# adc.net
KiCad netlist of a schematic drawn in Altium Designer
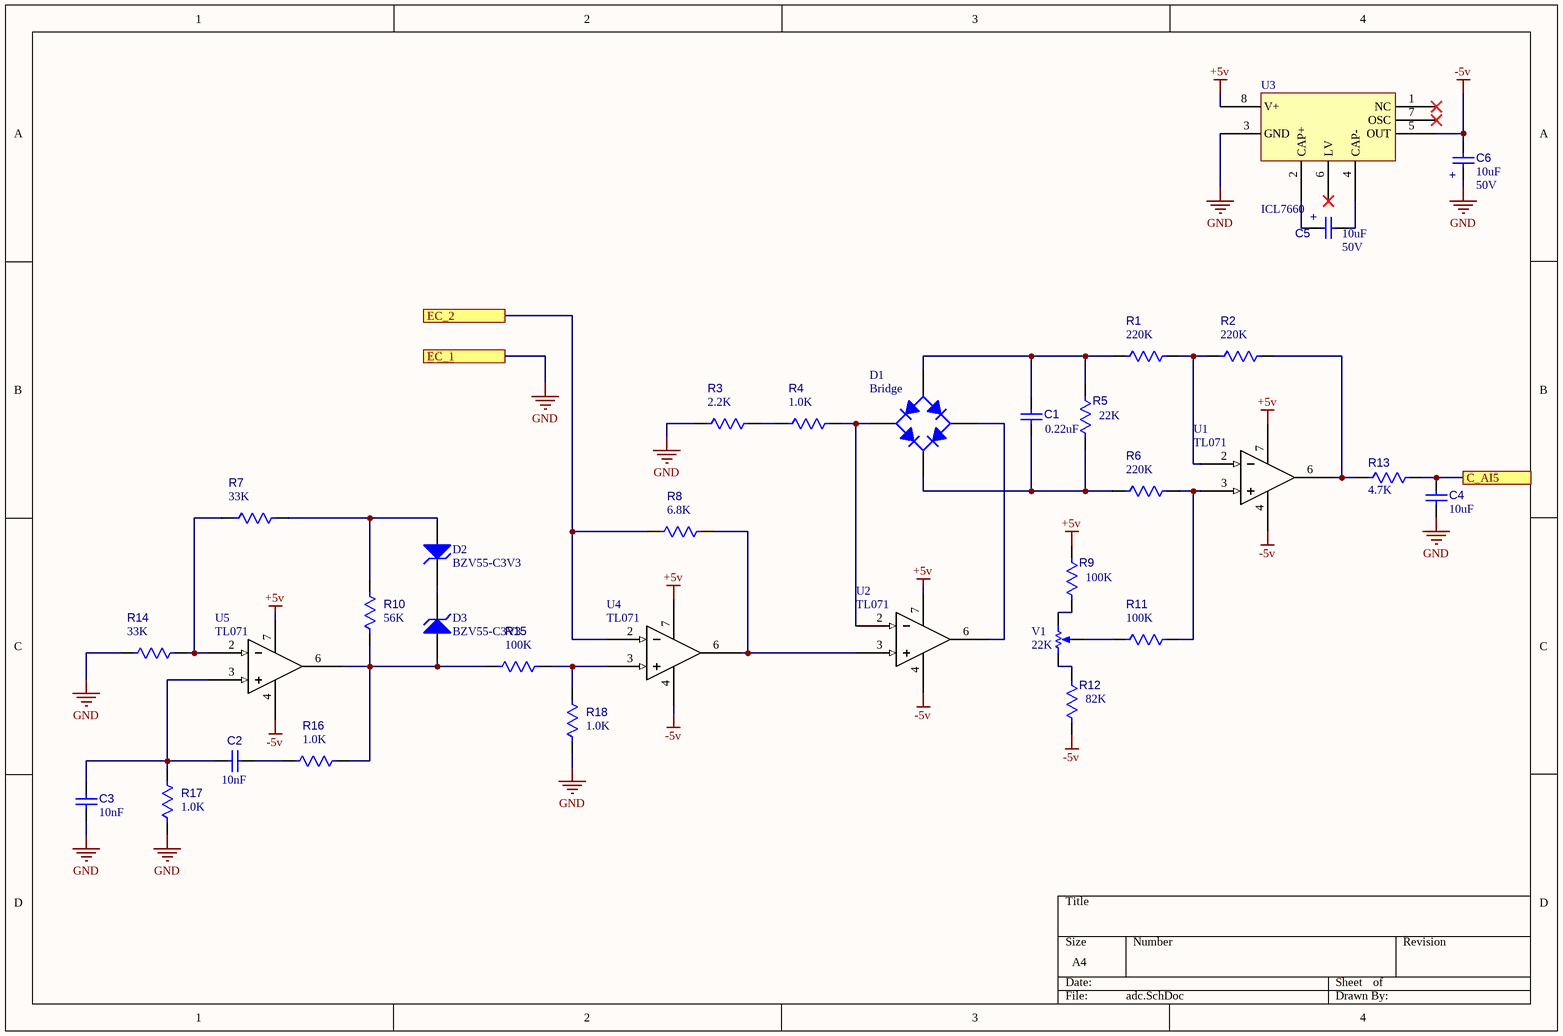
[diagram p0: adc.SchDoc]

(export (version "E")
  (design (tool "Eeschema 10.0.6"))
  (components
    (comp (ref "C1")
      (value "0.22uF")
      (footprint "0805")
      (description "Cap")
      (fields (field (name "TOLERANCE") "±10%"))
      (libsource (lib "mylib") (part "Cap"))
    )
    (comp (ref "C2")
      (value "10nF")
      (footprint "0805")
      (description "Cap")
      (fields (field (name "TOLERANCE") "±10%"))
      (libsource (lib "mylib") (part "Cap"))
    )
    (comp (ref "C3")
      (value "10nF")
      (footprint "0805")
      (description "Cap")
      (fields (field (name "TOLERANCE") "±10%"))
      (libsource (lib "mylib") (part "Cap"))
    )
    (comp (ref "C4")
      (value "10uF")
      (footprint "CAPC3216x130N")
      (description "Cap")
      (fields (field (name "TOLERANCE") "±10%"))
      (libsource (lib "mylib") (part "Cap"))
    )
    (comp (ref "C5")
      (value "10uF")
      (footprint "CAPC3216x130N")
      (description "Cap")
      (fields
        (field (name "TOLERANCE") "±10%")
        (field (name "MANUFACTURER") "Panasonic")
        (field (name "VOLTAGE-RATED") "50V")
      )
      (libsource (lib "mylib") (part "Cap Pol"))
    )
    (comp (ref "C6")
      (value "10uF")
      (footprint "CAPC3216x130N")
      (description "Cap")
      (fields
        (field (name "TOLERANCE") "±10%")
        (field (name "MANUFACTURER") "Panasonic")
        (field (name "VOLTAGE-RATED") "50V")
      )
      (libsource (lib "mylib") (part "Cap Pol"))
    )
    (comp (ref "D1")
      (value "Bridge")
      (footprint "BRIDGE_TO-269AA")
      (description "Full Wave Diode Bridge")
      (fields (field (name "PUBLISHER") "Altium Limited"))
      (libsource (lib "mylib") (part "Bridge"))
    )
    (comp (ref "D2")
      (value "BZV55-C3V3")
      (footprint "SOD80C")
      (description "Zener Diode 3.3v - SMD")
      (fields (field (name "PUBLISHER") "Altium Limited"))
      (libsource (lib "mylib") (part "D Zener"))
    )
    (comp (ref "D3")
      (value "BZV55-C3V3")
      (footprint "SOD80C")
      (description "Zener Diode 3.3v - SMD")
      (fields (field (name "PUBLISHER") "Altium Limited"))
      (libsource (lib "mylib") (part "D Zener"))
    )
    (comp (ref "R1")
      (value "220K")
      (footprint "0805")
      (description "Resistor")
      (fields (field (name "TOLERANCE") "1%"))
      (libsource (lib "mylib") (part "Res"))
    )
    (comp (ref "R2")
      (value "220K")
      (footprint "0805")
      (description "Resistor")
      (fields (field (name "TOLERANCE") "1%"))
      (libsource (lib "mylib") (part "Res"))
    )
    (comp (ref "R3")
      (value "2.2K")
      (footprint "0805")
      (description "Resistor")
      (fields (field (name "TOLERANCE") "1%"))
      (libsource (lib "mylib") (part "Res"))
    )
    (comp (ref "R4")
      (value "1.0K")
      (footprint "0805")
      (description "Resistor")
      (fields (field (name "TOLERANCE") "1%"))
      (libsource (lib "mylib") (part "Res"))
    )
    (comp (ref "R5")
      (value "22K")
      (footprint "0805")
      (description "Resistor")
      (fields (field (name "TOLERANCE") "1%"))
      (libsource (lib "mylib") (part "Res"))
    )
    (comp (ref "R6")
      (value "220K")
      (footprint "0805")
      (description "Resistor")
      (fields (field (name "TOLERANCE") "1%"))
      (libsource (lib "mylib") (part "Res"))
    )
    (comp (ref "R7")
      (value "33K")
      (footprint "0805")
      (description "Resistor")
      (fields (field (name "TOLERANCE") "1%"))
      (libsource (lib "mylib") (part "Res"))
    )
    (comp (ref "R8")
      (value "6.8K")
      (footprint "mylib:0603")
      (description "Resistor")
      (fields (field (name "TOLERANCE") "1%"))
      (libsource (lib "mylib") (part "Res"))
    )
    (comp (ref "R9")
      (value "100K")
      (footprint "0805")
      (description "Resistor")
      (fields (field (name "TOLERANCE") "1%"))
      (libsource (lib "mylib") (part "Res"))
    )
    (comp (ref "R10")
      (value "56K")
      (footprint "mylib:0603")
      (description "Resistor")
      (fields (field (name "TOLERANCE") "1%"))
      (libsource (lib "mylib") (part "Res"))
    )
    (comp (ref "R11")
      (value "100K")
      (footprint "0805")
      (description "Resistor")
      (fields (field (name "TOLERANCE") "1%"))
      (libsource (lib "mylib") (part "Res"))
    )
    (comp (ref "R12")
      (value "82K")
      (footprint "mylib:0603")
      (description "Resistor")
      (fields (field (name "TOLERANCE") "1%"))
      (libsource (lib "mylib") (part "Res"))
    )
    (comp (ref "R13")
      (value "4.7K")
      (footprint "0805")
      (description "Resistor")
      (fields (field (name "TOLERANCE") "1%"))
      (libsource (lib "mylib") (part "Res"))
    )
    (comp (ref "R14")
      (value "33K")
      (footprint "0805")
      (description "Resistor")
      (fields (field (name "TOLERANCE") "1%"))
      (libsource (lib "mylib") (part "Res"))
    )
    (comp (ref "R15")
      (value "100K")
      (footprint "0805")
      (description "Resistor")
      (fields (field (name "TOLERANCE") "1%"))
      (libsource (lib "mylib") (part "Res"))
    )
    (comp (ref "R16")
      (value "1.0K")
      (footprint "0805")
      (description "Resistor")
      (fields (field (name "TOLERANCE") "1%"))
      (libsource (lib "mylib") (part "Res"))
    )
    (comp (ref "R17")
      (value "1.0K")
      (footprint "0805")
      (description "Resistor")
      (fields (field (name "TOLERANCE") "1%"))
      (libsource (lib "mylib") (part "Res"))
    )
    (comp (ref "R18")
      (value "1.0K")
      (footprint "0805")
      (description "Resistor")
      (fields (field (name "TOLERANCE") "1%"))
      (libsource (lib "mylib") (part "Res"))
    )
    (comp (ref "U1")
      (value "TL071")
      (footprint "SO8_L")
      (description "Low-noise jfet-input operational amplifiers")
      (libsource (lib "mylib") (part "TL071"))
    )
    (comp (ref "U2")
      (value "TL071")
      (footprint "SO8_L")
      (description "Low-noise jfet-input operational amplifiers")
      (libsource (lib "mylib") (part "TL071"))
    )
    (comp (ref "U3")
      (value "ICL7660")
      (footprint "SO8_N")
      (description "CMOS Voltage Converters, from positive to negative for an input range of +1.5V to +10.0V")
      (libsource (lib "mylib") (part "ICL7660"))
    )
    (comp (ref "U4")
      (value "TL071")
      (footprint "SO8_L")
      (description "Low-noise jfet-input operational amplifiers")
      (libsource (lib "mylib") (part "TL071"))
    )
    (comp (ref "U5")
      (value "TL071")
      (footprint "SO8_L")
      (description "Low-noise jfet-input operational amplifiers")
      (libsource (lib "mylib") (part "TL071"))
    )
    (comp (ref "V1")
      (value "22K")
      (footprint "HDR1X3")
      (description "Potentiometer")
      (fields (field (name "PUBLISHER") "Altium Limited"))
      (libsource (lib "mylib") (part "Preset"))
    )
  )
  (nets
    (net (code "1") (name "+5v") (class "Default")
      (node (ref "R9") (pin "2") (pinfunction "2_2") (pintype "passive"))
      (node (ref "U1") (pin "7") (pinfunction "+Vcc_7") (pintype "passive"))
      (node (ref "U2") (pin "7") (pinfunction "+Vcc_7") (pintype "passive"))
      (node (ref "U3") (pin "8") (pinfunction "V+_8") (pintype "passive"))
      (node (ref "U4") (pin "7") (pinfunction "+Vcc_7") (pintype "passive"))
      (node (ref "U5") (pin "7") (pinfunction "+Vcc_7") (pintype "passive"))
    )
    (net (code "2") (name "-5v") (class "Default")
      (node (ref "C6") (pin "2") (pinfunction "2_2") (pintype "passive"))
      (node (ref "R12") (pin "1") (pinfunction "1_1") (pintype "passive"))
      (node (ref "U1") (pin "4") (pinfunction "-Vcc_4") (pintype "passive"))
      (node (ref "U2") (pin "4") (pinfunction "-Vcc_4") (pintype "passive"))
      (node (ref "U3") (pin "5") (pinfunction "OUT_5") (pintype "passive"))
      (node (ref "U4") (pin "4") (pinfunction "-Vcc_4") (pintype "passive"))
      (node (ref "U5") (pin "4") (pinfunction "-Vcc_4") (pintype "passive"))
    )
    (net (code "3") (name "/C_AI5") (class "Default")
      (node (ref "C4") (pin "1") (pinfunction "1_1") (pintype "passive"))
      (node (ref "R13") (pin "1") (pinfunction "1_1") (pintype "passive"))
    )
    (net (code "4") (name "/EC_2") (class "Default")
      (node (ref "R8") (pin "1") (pinfunction "1_1") (pintype "passive"))
      (node (ref "U4") (pin "2") (pinfunction "-_2") (pintype "input"))
    )
    (net (code "5") (name "GND") (class "Default")
      (node (ref "C3") (pin "2") (pinfunction "2_2") (pintype "passive"))
      (node (ref "C4") (pin "2") (pinfunction "2_2") (pintype "passive"))
      (node (ref "C6") (pin "1") (pinfunction "1_1") (pintype "passive"))
      (node (ref "R14") (pin "1") (pinfunction "1_1") (pintype "passive"))
      (node (ref "R17") (pin "2") (pinfunction "2_2") (pintype "passive"))
      (node (ref "R18") (pin "2") (pinfunction "2_2") (pintype "passive"))
      (node (ref "R3") (pin "1") (pinfunction "1_1") (pintype "passive"))
      (node (ref "U3") (pin "3") (pinfunction "GND_3") (pintype "passive"))
    )
    (net (code "6") (name "Net-(C2-Pad2)") (class "Default")
      (node (ref "C2") (pin "2") (pinfunction "2_2") (pintype "passive"))
      (node (ref "R16") (pin "1") (pinfunction "1_1") (pintype "passive"))
    )
    (net (code "7") (name "Net-(D1-A)") (class "Default")
      (node (ref "C1") (pin "1") (pinfunction "1_1") (pintype "passive"))
      (node (ref "D1") (pin "3") (pinfunction "A_3") (pintype "passive"))
      (node (ref "R1") (pin "1") (pinfunction "1_1") (pintype "passive"))
      (node (ref "R5") (pin "2") (pinfunction "2_2") (pintype "passive"))
    )
    (net (code "8") (name "Net-(D1-K)") (class "Default")
      (node (ref "C1") (pin "2") (pinfunction "2_2") (pintype "passive"))
      (node (ref "D1") (pin "1") (pinfunction "K_1") (pintype "passive"))
      (node (ref "R5") (pin "1") (pinfunction "1_1") (pintype "passive"))
      (node (ref "R6") (pin "1") (pinfunction "1_1") (pintype "passive"))
    )
    (net (code "9") (name "Net-(D2-A)") (class "Default")
      (node (ref "D2") (pin "1") (pinfunction "A_1") (pintype "passive"))
      (node (ref "R10") (pin "1") (pinfunction "1_1") (pintype "passive"))
      (node (ref "R7") (pin "2") (pinfunction "2_2") (pintype "passive"))
    )
    (net (code "10") (name "Net-(D2-K)") (class "Default")
      (node (ref "D2") (pin "2") (pinfunction "K_2") (pintype "passive"))
      (node (ref "D3") (pin "2") (pinfunction "K_2") (pintype "passive"))
    )
    (net (code "11") (name "Net-(D3-A)") (class "Default")
      (node (ref "D3") (pin "1") (pinfunction "A_1") (pintype "passive"))
      (node (ref "R10") (pin "2") (pinfunction "2_2") (pintype "passive"))
      (node (ref "R15") (pin "1") (pinfunction "1_1") (pintype "passive"))
      (node (ref "R16") (pin "2") (pinfunction "2_2") (pintype "passive"))
      (node (ref "U5") (pin "6") (pinfunction "output_6") (pintype "passive"))
    )
    (net (code "12") (name "Net-(R3-Pad2)") (class "Default")
      (node (ref "R3") (pin "2") (pinfunction "2_2") (pintype "passive"))
      (node (ref "R4") (pin "1") (pinfunction "1_1") (pintype "passive"))
    )
    (net (code "13") (name "Net-(U1-+)") (class "Default")
      (node (ref "R11") (pin "2") (pinfunction "2_2") (pintype "passive"))
      (node (ref "R6") (pin "2") (pinfunction "2_2") (pintype "passive"))
      (node (ref "U1") (pin "3") (pinfunction "+_3") (pintype "input"))
    )
    (net (code "14") (name "Net-(U1--)") (class "Default")
      (node (ref "R1") (pin "2") (pinfunction "2_2") (pintype "passive"))
      (node (ref "R2") (pin "1") (pinfunction "1_1") (pintype "passive"))
      (node (ref "U1") (pin "2") (pinfunction "-_2") (pintype "input"))
    )
    (net (code "15") (name "Net-(U1-output)") (class "Default")
      (node (ref "R13") (pin "2") (pinfunction "2_2") (pintype "passive"))
      (node (ref "R2") (pin "2") (pinfunction "2_2") (pintype "passive"))
      (node (ref "U1") (pin "6") (pinfunction "output_6") (pintype "passive"))
    )
    (net (code "16") (name "Net-(U2-+)") (class "Default")
      (node (ref "R8") (pin "2") (pinfunction "2_2") (pintype "passive"))
      (node (ref "U2") (pin "3") (pinfunction "+_3") (pintype "input"))
      (node (ref "U4") (pin "6") (pinfunction "output_6") (pintype "passive"))
    )
    (net (code "17") (name "Net-(U2--)") (class "Default")
      (node (ref "D1") (pin "2") (pinfunction "C_2") (pintype "passive"))
      (node (ref "R4") (pin "2") (pinfunction "2_2") (pintype "passive"))
      (node (ref "U2") (pin "2") (pinfunction "-_2") (pintype "input"))
    )
    (net (code "18") (name "Net-(U2-output)") (class "Default")
      (node (ref "D1") (pin "4") (pinfunction "C_4") (pintype "passive"))
      (node (ref "U2") (pin "6") (pinfunction "output_6") (pintype "passive"))
    )
    (net (code "19") (name "Net-(U3-CAP+)") (class "Default")
      (node (ref "C5") (pin "1") (pinfunction "1_1") (pintype "passive"))
      (node (ref "U3") (pin "2") (pinfunction "CAP+_2") (pintype "passive"))
    )
    (net (code "20") (name "Net-(U3-CAP-)") (class "Default")
      (node (ref "C5") (pin "2") (pinfunction "2_2") (pintype "passive"))
      (node (ref "U3") (pin "4") (pinfunction "CAP-_4") (pintype "passive"))
    )
    (net (code "21") (name "Net-(U4-+)") (class "Default")
      (node (ref "R15") (pin "2") (pinfunction "2_2") (pintype "passive"))
      (node (ref "R18") (pin "1") (pinfunction "1_1") (pintype "passive"))
      (node (ref "U4") (pin "3") (pinfunction "+_3") (pintype "input"))
    )
    (net (code "22") (name "Net-(U5-+)") (class "Default")
      (node (ref "C2") (pin "1") (pinfunction "1_1") (pintype "passive"))
      (node (ref "C3") (pin "1") (pinfunction "1_1") (pintype "passive"))
      (node (ref "R17") (pin "1") (pinfunction "1_1") (pintype "passive"))
      (node (ref "U5") (pin "3") (pinfunction "+_3") (pintype "input"))
    )
    (net (code "23") (name "Net-(U5--)") (class "Default")
      (node (ref "R14") (pin "2") (pinfunction "2_2") (pintype "passive"))
      (node (ref "R7") (pin "1") (pinfunction "1_1") (pintype "passive"))
      (node (ref "U5") (pin "2") (pinfunction "-_2") (pintype "input"))
    )
    (net (code "24") (name "Net-(V1-BOT)") (class "Default")
      (node (ref "R9") (pin "1") (pinfunction "1_1") (pintype "passive"))
      (node (ref "V1") (pin "3") (pinfunction "BOT_3") (pintype "passive"))
    )
    (net (code "25") (name "Net-(V1-TAP)") (class "Default")
      (node (ref "R11") (pin "1") (pinfunction "1_1") (pintype "passive"))
      (node (ref "V1") (pin "2") (pinfunction "TAP_2") (pintype "passive"))
    )
    (net (code "26") (name "Net-(V1-TOP)") (class "Default")
      (node (ref "R12") (pin "2") (pinfunction "2_2") (pintype "passive"))
      (node (ref "V1") (pin "1") (pinfunction "TOP_1") (pintype "passive"))
    )
    (net (code "27") (name "unconnected-(U3-LV-Pad6)") (class "Default")
      (node (ref "U3") (pin "6") (pinfunction "LV_6") (pintype "passive+no_connect"))
    )
    (net (code "28") (name "unconnected-(U3-NC-Pad1)") (class "Default")
      (node (ref "U3") (pin "1") (pinfunction "NC_1") (pintype "passive+no_connect"))
    )
    (net (code "29") (name "unconnected-(U3-OSC-Pad7)") (class "Default")
      (node (ref "U3") (pin "7") (pinfunction "OSC_7") (pintype "passive+no_connect"))
    )
  )
)
